# VOLTAGE_MEASURE_DC.net
KiCad netlist of a schematic drawn in Altium Designer
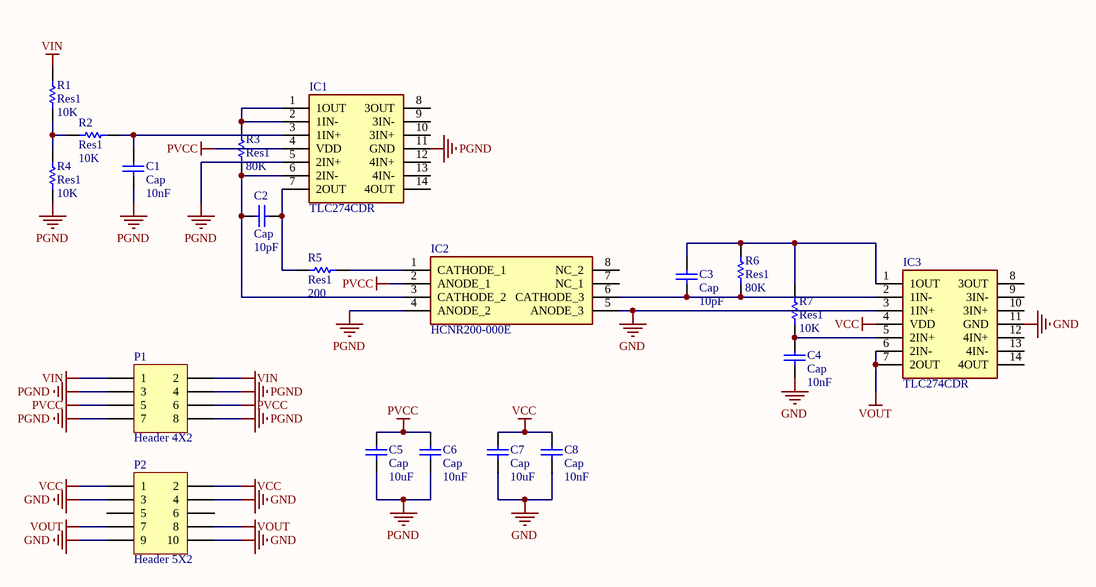
[diagram p0: VOLTAGE_MEASURE_DC.SchDoc]

(export (version "E")
  (design (tool "Eeschema 10.0.6"))
  (components
    (comp (ref "C1")
      (value "Cap")
      (footprint "1608[0603]")
      (description "Capacitor")
      (fields (field (name "ALTIUM_VALUE") "10nF") (field (name "PUBLISHER") "Altium Limited"))
      (libsource (lib "Miscellaneous Devices") (part "Cap"))
    )
    (comp (ref "C2")
      (value "Cap")
      (footprint "1608[0603]")
      (description "Capacitor")
      (fields (field (name "ALTIUM_VALUE") "10pF") (field (name "PUBLISHER") "Altium Limited"))
      (libsource (lib "Miscellaneous Devices") (part "Cap"))
    )
    (comp (ref "C3")
      (value "Cap")
      (footprint "1608[0603]")
      (description "Capacitor")
      (fields (field (name "ALTIUM_VALUE") "10pF") (field (name "PUBLISHER") "Altium Limited"))
      (libsource (lib "Miscellaneous Devices") (part "Cap"))
    )
    (comp (ref "C4")
      (value "Cap")
      (footprint "1608[0603]")
      (description "Capacitor")
      (fields (field (name "ALTIUM_VALUE") "10nF") (field (name "PUBLISHER") "Altium Limited"))
      (libsource (lib "Miscellaneous Devices") (part "Cap"))
    )
    (comp (ref "C5")
      (value "Cap")
      (footprint "1608[0603]")
      (description "Capacitor")
      (fields (field (name "ALTIUM_VALUE") "10uF") (field (name "PUBLISHER") "Altium Limited"))
      (libsource (lib "Miscellaneous Devices") (part "Cap"))
    )
    (comp (ref "C6")
      (value "Cap")
      (footprint "1608[0603]")
      (description "Capacitor")
      (fields (field (name "ALTIUM_VALUE") "10nF") (field (name "PUBLISHER") "Altium Limited"))
      (libsource (lib "Miscellaneous Devices") (part "Cap"))
    )
    (comp (ref "C7")
      (value "Cap")
      (footprint "1608[0603]")
      (description "Capacitor")
      (fields (field (name "ALTIUM_VALUE") "10uF") (field (name "PUBLISHER") "Altium Limited"))
      (libsource (lib "Miscellaneous Devices") (part "Cap"))
    )
    (comp (ref "C8")
      (value "Cap")
      (footprint "1608[0603]")
      (description "Capacitor")
      (fields (field (name "ALTIUM_VALUE") "10nF") (field (name "PUBLISHER") "Altium Limited"))
      (libsource (lib "Miscellaneous Devices") (part "Cap"))
    )
    (comp (ref "IC1")
      (value "TLC274CDR")
      (footprint "SamacSys:SOIC127P600X175-14N")
      (description "Integrated Circuit")
      (fields (field (name "MOUSER PART NUMBER") "595-TLC274CDR") (field (name "RS PART NUMBER") "0527237"))
      (libsource (lib "*") (part "TLC274CDR"))
    )
    (comp (ref "IC2")
      (value "HCNR200-000E")
      (footprint "SamacSys:DIP1100W56P254L1115H510Q8N")
      (description "Integrated Circuit")
      (fields
        (field (name "MOUSER PART NUMBER") "630-HCNR200-000E")
        (field (name "RS PART NUMBER") "6961248P")
      )
      (libsource (lib "*") (part "HCNR200-000E"))
    )
    (comp (ref "IC3")
      (value "TLC274CDR")
      (footprint "SamacSys:SOIC127P600X175-14N")
      (description "Integrated Circuit")
      (fields (field (name "MOUSER PART NUMBER") "595-TLC274CDR") (field (name "RS PART NUMBER") "0527237"))
      (libsource (lib "*") (part "TLC274CDR"))
    )
    (comp (ref "P1")
      (value "Header 4X2")
      (footprint "HDR2X4")
      (description "Header, 4-Pin, Dual row")
      (fields (field (name "PUBLISHER") "Altium Limited"))
      (libsource (lib "Miscellaneous Connectors") (part "Header 4X2"))
    )
    (comp (ref "P2")
      (value "Header 5X2")
      (footprint "HDR2X5")
      (description "Header, 5-Pin, Dual row")
      (fields (field (name "PUBLISHER") "Altium Limited"))
      (libsource (lib "Miscellaneous Connectors") (part "Header 5X2"))
    )
    (comp (ref "R1")
      (value "Res1")
      (footprint "J1-0603")
      (description "Resistor")
      (fields (field (name "ALTIUM_VALUE") "10K") (field (name "PUBLISHER") "Altium Limited"))
      (libsource (lib "Miscellaneous Devices") (part "Res1"))
    )
    (comp (ref "R2")
      (value "Res1")
      (footprint "J1-0603")
      (description "Resistor")
      (fields (field (name "ALTIUM_VALUE") "10K") (field (name "PUBLISHER") "Altium Limited"))
      (libsource (lib "Miscellaneous Devices") (part "Res1"))
    )
    (comp (ref "R3")
      (value "Res1")
      (footprint "J1-0603")
      (description "Resistor")
      (fields (field (name "ALTIUM_VALUE") "80K") (field (name "PUBLISHER") "Altium Limited"))
      (libsource (lib "Miscellaneous Devices") (part "Res1"))
    )
    (comp (ref "R4")
      (value "Res1")
      (footprint "J1-0603")
      (description "Resistor")
      (fields (field (name "ALTIUM_VALUE") "10K") (field (name "PUBLISHER") "Altium Limited"))
      (libsource (lib "Miscellaneous Devices") (part "Res1"))
    )
    (comp (ref "R5")
      (value "Res1")
      (footprint "J1-0603")
      (description "Resistor")
      (fields (field (name "ALTIUM_VALUE") "200") (field (name "PUBLISHER") "Altium Limited"))
      (libsource (lib "Miscellaneous Devices") (part "Res1"))
    )
    (comp (ref "R6")
      (value "Res1")
      (footprint "J1-0603")
      (description "Resistor")
      (fields (field (name "ALTIUM_VALUE") "80K") (field (name "PUBLISHER") "Altium Limited"))
      (libsource (lib "Miscellaneous Devices") (part "Res1"))
    )
    (comp (ref "R7")
      (value "Res1")
      (footprint "J1-0603")
      (description "Resistor")
      (fields (field (name "ALTIUM_VALUE") "10K") (field (name "PUBLISHER") "Altium Limited"))
      (libsource (lib "Miscellaneous Devices") (part "Res1"))
    )
  )
  (nets
    (net (code "1") (name "GND") (class "Default")
      (node (ref "C4") (pin "1") (pinfunction "1_1") (pintype "passive"))
      (node (ref "C7") (pin "2") (pinfunction "2_2") (pintype "passive"))
      (node (ref "C8") (pin "2") (pinfunction "2_2") (pintype "passive"))
      (node (ref "IC2") (pin "5") (pinfunction "ANODE_3_5") (pintype "passive"))
      (node (ref "IC3") (pin "11") (pinfunction "GND_11") (pintype "passive"))
      (node (ref "IC3") (pin "3") (pinfunction "1IN+_3") (pintype "passive"))
      (node (ref "P2") (pin "10") (pinfunction "10_10") (pintype "passive"))
      (node (ref "P2") (pin "3") (pinfunction "3_3") (pintype "passive"))
      (node (ref "P2") (pin "4") (pinfunction "4_4") (pintype "passive"))
      (node (ref "P2") (pin "9") (pinfunction "9_9") (pintype "passive"))
    )
    (net (code "2") (name "Net-(IC1-1IN+)") (class "Default")
      (node (ref "C1") (pin "2") (pinfunction "2_2") (pintype "passive"))
      (node (ref "IC1") (pin "3") (pinfunction "1IN+_3") (pintype "passive"))
      (node (ref "R2") (pin "2") (pinfunction "2_2") (pintype "passive"))
    )
    (net (code "3") (name "Net-(IC1-1IN-)") (class "Default")
      (node (ref "IC1") (pin "1") (pinfunction "1OUT_1") (pintype "passive"))
      (node (ref "IC1") (pin "2") (pinfunction "1IN-_2") (pintype "passive"))
      (node (ref "R3") (pin "2") (pinfunction "2_2") (pintype "passive"))
    )
    (net (code "4") (name "Net-(IC1-2IN-)") (class "Default")
      (node (ref "C2") (pin "2") (pinfunction "2_2") (pintype "passive"))
      (node (ref "IC1") (pin "6") (pinfunction "2IN-_6") (pintype "passive"))
      (node (ref "IC2") (pin "3") (pinfunction "CATHODE_2_3") (pintype "passive"))
      (node (ref "R3") (pin "1") (pinfunction "1_1") (pintype "passive"))
    )
    (net (code "5") (name "Net-(IC1-2OUT)") (class "Default")
      (node (ref "C2") (pin "1") (pinfunction "1_1") (pintype "passive"))
      (node (ref "IC1") (pin "7") (pinfunction "2OUT_7") (pintype "passive"))
      (node (ref "R5") (pin "1") (pinfunction "1_1") (pintype "passive"))
    )
    (net (code "6") (name "Net-(IC2-CATHODE_1)") (class "Default")
      (node (ref "IC2") (pin "1") (pinfunction "CATHODE_1_1") (pintype "passive"))
      (node (ref "R5") (pin "2") (pinfunction "2_2") (pintype "passive"))
    )
    (net (code "7") (name "Net-(IC2-CATHODE_3)") (class "Default")
      (node (ref "C3") (pin "2") (pinfunction "2_2") (pintype "passive"))
      (node (ref "IC2") (pin "6") (pinfunction "CATHODE_3_6") (pintype "passive"))
      (node (ref "IC3") (pin "2") (pinfunction "1IN-_2") (pintype "passive"))
      (node (ref "R6") (pin "1") (pinfunction "1_1") (pintype "passive"))
    )
    (net (code "8") (name "Net-(IC3-1OUT)") (class "Default")
      (node (ref "C3") (pin "1") (pinfunction "1_1") (pintype "passive"))
      (node (ref "IC3") (pin "1") (pinfunction "1OUT_1") (pintype "passive"))
      (node (ref "R6") (pin "2") (pinfunction "2_2") (pintype "passive"))
      (node (ref "R7") (pin "1") (pinfunction "1_1") (pintype "passive"))
    )
    (net (code "9") (name "Net-(IC3-2IN+)") (class "Default")
      (node (ref "C4") (pin "2") (pinfunction "2_2") (pintype "passive"))
      (node (ref "IC3") (pin "5") (pinfunction "2IN+_5") (pintype "passive"))
      (node (ref "R7") (pin "2") (pinfunction "2_2") (pintype "passive"))
    )
    (net (code "10") (name "Net-(R1-Pad1)") (class "Default")
      (node (ref "R1") (pin "1") (pinfunction "1_1") (pintype "passive"))
      (node (ref "R2") (pin "1") (pinfunction "1_1") (pintype "passive"))
      (node (ref "R4") (pin "2") (pinfunction "2_2") (pintype "passive"))
    )
    (net (code "11") (name "PGND") (class "Default")
      (node (ref "C1") (pin "1") (pinfunction "1_1") (pintype "passive"))
      (node (ref "C5") (pin "2") (pinfunction "2_2") (pintype "passive"))
      (node (ref "C6") (pin "2") (pinfunction "2_2") (pintype "passive"))
      (node (ref "IC1") (pin "11") (pinfunction "GND_11") (pintype "passive"))
      (node (ref "IC1") (pin "5") (pinfunction "2IN+_5") (pintype "passive"))
      (node (ref "IC2") (pin "4") (pinfunction "ANODE_2_4") (pintype "passive"))
      (node (ref "P1") (pin "3") (pinfunction "3_3") (pintype "passive"))
      (node (ref "P1") (pin "4") (pinfunction "4_4") (pintype "passive"))
      (node (ref "P1") (pin "7") (pinfunction "7_7") (pintype "passive"))
      (node (ref "P1") (pin "8") (pinfunction "8_8") (pintype "passive"))
      (node (ref "R4") (pin "1") (pinfunction "1_1") (pintype "passive"))
    )
    (net (code "12") (name "PVCC") (class "Default")
      (node (ref "C5") (pin "1") (pinfunction "1_1") (pintype "passive"))
      (node (ref "C6") (pin "1") (pinfunction "1_1") (pintype "passive"))
      (node (ref "IC1") (pin "4") (pinfunction "VDD_4") (pintype "passive"))
      (node (ref "IC2") (pin "2") (pinfunction "ANODE_1_2") (pintype "passive"))
      (node (ref "P1") (pin "5") (pinfunction "5_5") (pintype "passive"))
      (node (ref "P1") (pin "6") (pinfunction "6_6") (pintype "passive"))
    )
    (net (code "13") (name "VCC") (class "Default")
      (node (ref "C7") (pin "1") (pinfunction "1_1") (pintype "passive"))
      (node (ref "C8") (pin "1") (pinfunction "1_1") (pintype "passive"))
      (node (ref "IC3") (pin "4") (pinfunction "VDD_4") (pintype "passive"))
      (node (ref "P2") (pin "1") (pinfunction "1_1") (pintype "passive"))
      (node (ref "P2") (pin "2") (pinfunction "2_2") (pintype "passive"))
    )
    (net (code "14") (name "VIN") (class "Default")
      (node (ref "P1") (pin "1") (pinfunction "1_1") (pintype "passive"))
      (node (ref "P1") (pin "2") (pinfunction "2_2") (pintype "passive"))
      (node (ref "R1") (pin "2") (pinfunction "2_2") (pintype "passive"))
    )
    (net (code "15") (name "VOUT") (class "Default")
      (node (ref "IC3") (pin "6") (pinfunction "2IN-_6") (pintype "passive"))
      (node (ref "IC3") (pin "7") (pinfunction "2OUT_7") (pintype "passive"))
      (node (ref "P2") (pin "7") (pinfunction "7_7") (pintype "passive"))
      (node (ref "P2") (pin "8") (pinfunction "8_8") (pintype "passive"))
    )
    (net (code "16") (name "unconnected-(IC1-3IN+-Pad10)") (class "Default")
      (node (ref "IC1") (pin "10") (pinfunction "3IN+_10") (pintype "passive"))
    )
    (net (code "17") (name "unconnected-(IC1-3IN--Pad9)") (class "Default")
      (node (ref "IC1") (pin "9") (pinfunction "3IN-_9") (pintype "passive"))
    )
    (net (code "18") (name "unconnected-(IC1-3OUT-Pad8)") (class "Default")
      (node (ref "IC1") (pin "8") (pinfunction "3OUT_8") (pintype "passive"))
    )
    (net (code "19") (name "unconnected-(IC1-4IN+-Pad12)") (class "Default")
      (node (ref "IC1") (pin "12") (pinfunction "4IN+_12") (pintype "passive"))
    )
    (net (code "20") (name "unconnected-(IC1-4IN--Pad13)") (class "Default")
      (node (ref "IC1") (pin "13") (pinfunction "4IN-_13") (pintype "passive"))
    )
    (net (code "21") (name "unconnected-(IC1-4OUT-Pad14)") (class "Default")
      (node (ref "IC1") (pin "14") (pinfunction "4OUT_14") (pintype "passive"))
    )
    (net (code "22") (name "unconnected-(IC2-NC_1-Pad7)") (class "Default")
      (node (ref "IC2") (pin "7") (pinfunction "NC_1_7") (pintype "passive"))
    )
    (net (code "23") (name "unconnected-(IC2-NC_2-Pad8)") (class "Default")
      (node (ref "IC2") (pin "8") (pinfunction "NC_2_8") (pintype "passive"))
    )
    (net (code "24") (name "unconnected-(IC3-3IN+-Pad10)") (class "Default")
      (node (ref "IC3") (pin "10") (pinfunction "3IN+_10") (pintype "passive"))
    )
    (net (code "25") (name "unconnected-(IC3-3IN--Pad9)") (class "Default")
      (node (ref "IC3") (pin "9") (pinfunction "3IN-_9") (pintype "passive"))
    )
    (net (code "26") (name "unconnected-(IC3-3OUT-Pad8)") (class "Default")
      (node (ref "IC3") (pin "8") (pinfunction "3OUT_8") (pintype "passive"))
    )
    (net (code "27") (name "unconnected-(IC3-4IN+-Pad12)") (class "Default")
      (node (ref "IC3") (pin "12") (pinfunction "4IN+_12") (pintype "passive"))
    )
    (net (code "28") (name "unconnected-(IC3-4IN--Pad13)") (class "Default")
      (node (ref "IC3") (pin "13") (pinfunction "4IN-_13") (pintype "passive"))
    )
    (net (code "29") (name "unconnected-(IC3-4OUT-Pad14)") (class "Default")
      (node (ref "IC3") (pin "14") (pinfunction "4OUT_14") (pintype "passive"))
    )
    (net (code "30") (name "unconnected-(P2-Pad5)") (class "Default")
      (node (ref "P2") (pin "5") (pinfunction "5_5") (pintype "passive"))
    )
    (net (code "31") (name "unconnected-(P2-Pad6)") (class "Default")
      (node (ref "P2") (pin "6") (pinfunction "6_6") (pintype "passive"))
    )
  )
)
